# Tannenbaum.net
KiCad netlist of a schematic drawn in EAGLE
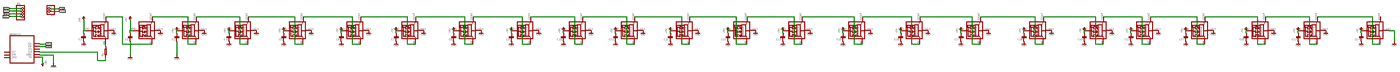
[diagram p0: schematic, sheet 1, overview]
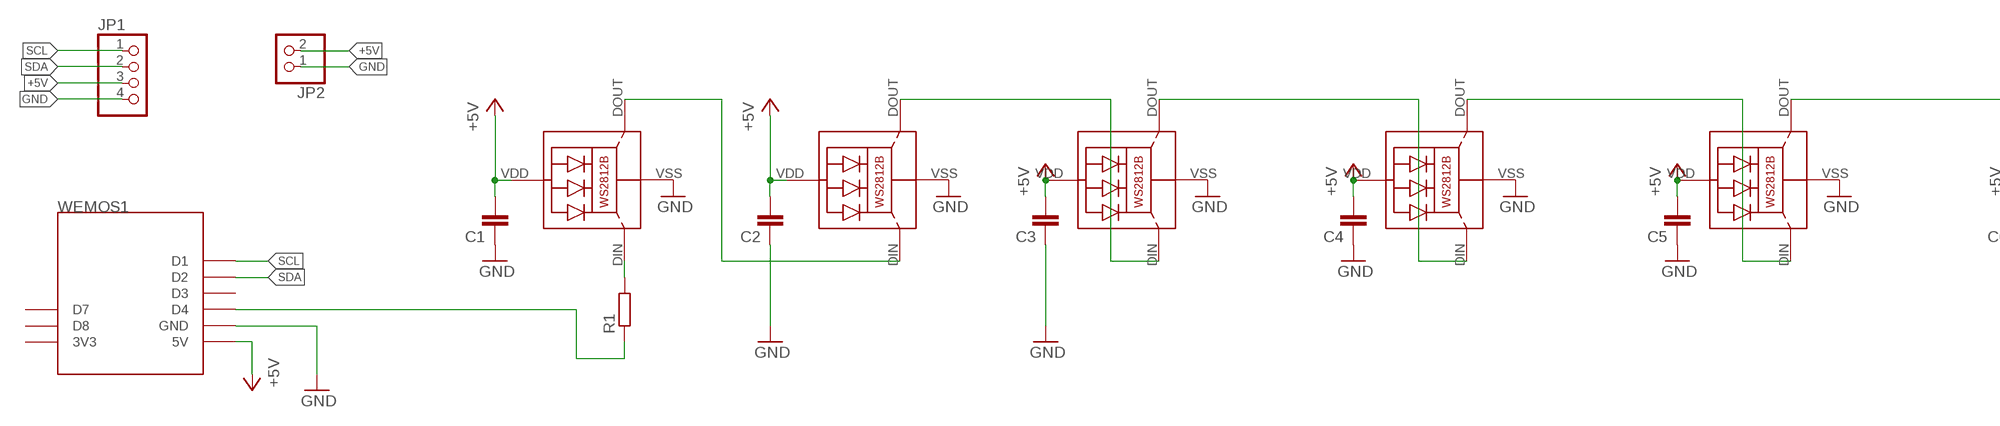
[diagram p1: schematic, sheet 1, part 1 of 4]
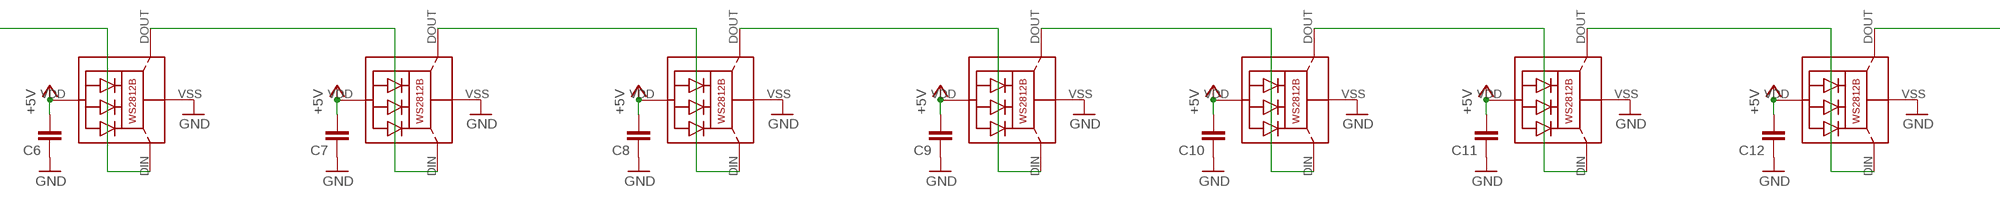
[diagram p2: schematic, sheet 1, part 2 of 4]
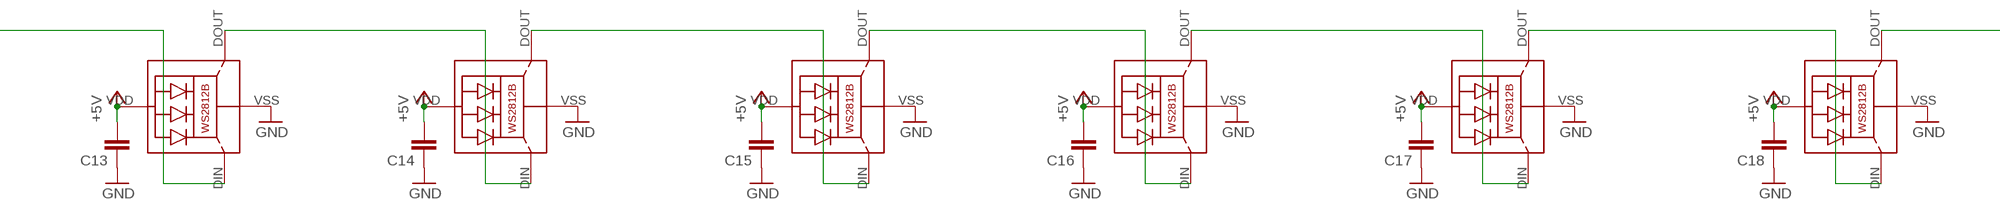
[diagram p3: schematic, sheet 1, part 3 of 4]
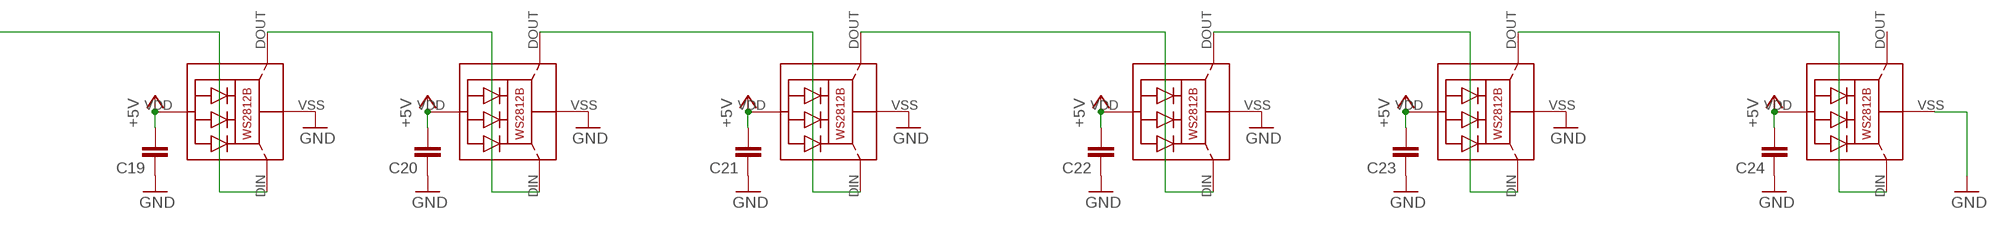
[diagram p4: schematic, sheet 1, part 4 of 4]

(export (version "E")
  (design (tool "Eeschema 10.0.6"))
  (components
    (comp (ref "C1")
      (value "C-EUC0805")
      (footprint "eagle-import:C0805")
      (libsource (lib "eagle-import") (part "C-EUC0805"))
    )
    (comp (ref "C2")
      (value "C-EUC0805")
      (footprint "eagle-import:C0805")
      (libsource (lib "eagle-import") (part "C-EUC0805"))
    )
    (comp (ref "C3")
      (value "C-EUC0805")
      (footprint "eagle-import:C0805")
      (libsource (lib "eagle-import") (part "C-EUC0805"))
    )
    (comp (ref "C4")
      (value "C-EUC0805")
      (footprint "eagle-import:C0805")
      (libsource (lib "eagle-import") (part "C-EUC0805"))
    )
    (comp (ref "C5")
      (value "C-EUC0805")
      (footprint "eagle-import:C0805")
      (libsource (lib "eagle-import") (part "C-EUC0805"))
    )
    (comp (ref "C6")
      (value "C-EUC0805")
      (footprint "eagle-import:C0805")
      (libsource (lib "eagle-import") (part "C-EUC0805"))
    )
    (comp (ref "C7")
      (value "C-EUC0805")
      (footprint "eagle-import:C0805")
      (libsource (lib "eagle-import") (part "C-EUC0805"))
    )
    (comp (ref "C8")
      (value "C-EUC0805")
      (footprint "eagle-import:C0805")
      (libsource (lib "eagle-import") (part "C-EUC0805"))
    )
    (comp (ref "C9")
      (value "C-EUC0805")
      (footprint "eagle-import:C0805")
      (libsource (lib "eagle-import") (part "C-EUC0805"))
    )
    (comp (ref "C10")
      (value "C-EUC0805")
      (footprint "eagle-import:C0805")
      (libsource (lib "eagle-import") (part "C-EUC0805"))
    )
    (comp (ref "C11")
      (value "C-EUC0805")
      (footprint "eagle-import:C0805")
      (libsource (lib "eagle-import") (part "C-EUC0805"))
    )
    (comp (ref "C12")
      (value "C-EUC0805")
      (footprint "eagle-import:C0805")
      (libsource (lib "eagle-import") (part "C-EUC0805"))
    )
    (comp (ref "C13")
      (value "C-EUC0805")
      (footprint "eagle-import:C0805")
      (libsource (lib "eagle-import") (part "C-EUC0805"))
    )
    (comp (ref "C14")
      (value "C-EUC0805")
      (footprint "eagle-import:C0805")
      (libsource (lib "eagle-import") (part "C-EUC0805"))
    )
    (comp (ref "C15")
      (value "C-EUC0805")
      (footprint "eagle-import:C0805")
      (libsource (lib "eagle-import") (part "C-EUC0805"))
    )
    (comp (ref "C16")
      (value "C-EUC0805")
      (footprint "eagle-import:C0805")
      (libsource (lib "eagle-import") (part "C-EUC0805"))
    )
    (comp (ref "C17")
      (value "C-EUC0805")
      (footprint "eagle-import:C0805")
      (libsource (lib "eagle-import") (part "C-EUC0805"))
    )
    (comp (ref "C18")
      (value "C-EUC0805")
      (footprint "eagle-import:C0805")
      (libsource (lib "eagle-import") (part "C-EUC0805"))
    )
    (comp (ref "C19")
      (value "C-EUC0805")
      (footprint "eagle-import:C0805")
      (libsource (lib "eagle-import") (part "C-EUC0805"))
    )
    (comp (ref "C20")
      (value "C-EUC0805")
      (footprint "eagle-import:C0805")
      (libsource (lib "eagle-import") (part "C-EUC0805"))
    )
    (comp (ref "C21")
      (value "C-EUC0805")
      (footprint "eagle-import:C0805")
      (libsource (lib "eagle-import") (part "C-EUC0805"))
    )
    (comp (ref "C22")
      (value "C-EUC0805")
      (footprint "eagle-import:C0805")
      (libsource (lib "eagle-import") (part "C-EUC0805"))
    )
    (comp (ref "C23")
      (value "C-EUC0805")
      (footprint "eagle-import:C0805")
      (libsource (lib "eagle-import") (part "C-EUC0805"))
    )
    (comp (ref "C24")
      (value "C-EUC0805")
      (footprint "eagle-import:C0805")
      (libsource (lib "eagle-import") (part "C-EUC0805"))
    )
    (comp (ref "JP1")
      (value "PINHD-1X4")
      (footprint "eagle-import:1X04")
      (libsource (lib "eagle-import") (part "PINHD-1X4"))
    )
    (comp (ref "JP2")
      (value "PINHD-1X2")
      (footprint "eagle-import:1X02")
      (libsource (lib "eagle-import") (part "PINHD-1X2"))
    )
    (comp (ref "LED1")
      (value "WS2812B")
      (footprint "eagle-import:WS2812B")
      (libsource (lib "eagle-import") (part "WS2812B"))
    )
    (comp (ref "LED2")
      (value "WS2812B")
      (footprint "eagle-import:WS2812B")
      (libsource (lib "eagle-import") (part "WS2812B"))
    )
    (comp (ref "LED3")
      (value "WS2812B")
      (footprint "eagle-import:WS2812B")
      (libsource (lib "eagle-import") (part "WS2812B"))
    )
    (comp (ref "LED4")
      (value "WS2812B")
      (footprint "eagle-import:WS2812B")
      (libsource (lib "eagle-import") (part "WS2812B"))
    )
    (comp (ref "LED5")
      (value "WS2812B")
      (footprint "eagle-import:WS2812B")
      (libsource (lib "eagle-import") (part "WS2812B"))
    )
    (comp (ref "LED6")
      (value "WS2812B")
      (footprint "eagle-import:WS2812B")
      (libsource (lib "eagle-import") (part "WS2812B"))
    )
    (comp (ref "LED7")
      (value "WS2812B")
      (footprint "eagle-import:WS2812B")
      (libsource (lib "eagle-import") (part "WS2812B"))
    )
    (comp (ref "LED8")
      (value "WS2812B")
      (footprint "eagle-import:WS2812B")
      (libsource (lib "eagle-import") (part "WS2812B"))
    )
    (comp (ref "LED9")
      (value "WS2812B")
      (footprint "eagle-import:WS2812B")
      (libsource (lib "eagle-import") (part "WS2812B"))
    )
    (comp (ref "LED10")
      (value "WS2812B")
      (footprint "eagle-import:WS2812B")
      (libsource (lib "eagle-import") (part "WS2812B"))
    )
    (comp (ref "LED11")
      (value "WS2812B")
      (footprint "eagle-import:WS2812B")
      (libsource (lib "eagle-import") (part "WS2812B"))
    )
    (comp (ref "LED12")
      (value "WS2812B")
      (footprint "eagle-import:WS2812B")
      (libsource (lib "eagle-import") (part "WS2812B"))
    )
    (comp (ref "LED13")
      (value "WS2812B")
      (footprint "eagle-import:WS2812B")
      (libsource (lib "eagle-import") (part "WS2812B"))
    )
    (comp (ref "LED14")
      (value "WS2812B")
      (footprint "eagle-import:WS2812B")
      (libsource (lib "eagle-import") (part "WS2812B"))
    )
    (comp (ref "LED15")
      (value "WS2812B")
      (footprint "eagle-import:WS2812B")
      (libsource (lib "eagle-import") (part "WS2812B"))
    )
    (comp (ref "LED16")
      (value "WS2812B")
      (footprint "eagle-import:WS2812B")
      (libsource (lib "eagle-import") (part "WS2812B"))
    )
    (comp (ref "LED17")
      (value "WS2812B")
      (footprint "eagle-import:WS2812B")
      (libsource (lib "eagle-import") (part "WS2812B"))
    )
    (comp (ref "LED18")
      (value "WS2812B")
      (footprint "eagle-import:WS2812B")
      (libsource (lib "eagle-import") (part "WS2812B"))
    )
    (comp (ref "LED19")
      (value "WS2812B")
      (footprint "eagle-import:WS2812B")
      (libsource (lib "eagle-import") (part "WS2812B"))
    )
    (comp (ref "LED20")
      (value "WS2812B")
      (footprint "eagle-import:WS2812B")
      (libsource (lib "eagle-import") (part "WS2812B"))
    )
    (comp (ref "LED21")
      (value "WS2812B")
      (footprint "eagle-import:WS2812B")
      (libsource (lib "eagle-import") (part "WS2812B"))
    )
    (comp (ref "LED22")
      (value "WS2812B")
      (footprint "eagle-import:WS2812B")
      (libsource (lib "eagle-import") (part "WS2812B"))
    )
    (comp (ref "LED23")
      (value "WS2812B")
      (footprint "eagle-import:WS2812B")
      (libsource (lib "eagle-import") (part "WS2812B"))
    )
    (comp (ref "LED24")
      (value "WS2812B")
      (footprint "eagle-import:WS2812B")
      (libsource (lib "eagle-import") (part "WS2812B"))
    )
    (comp (ref "R1")
      (value "R-EU_R0805")
      (footprint "eagle-import:R0805")
      (libsource (lib "eagle-import") (part "R-EU_R0805"))
    )
    (comp (ref "WEMOS1")
      (value "WEMOS-D1-MINI1")
      (footprint "eagle-import:WEMOS-D1-MINI1")
      (fields (field (name "SPICEPREFIX") "X"))
      (libsource (lib "eagle-import") (part "WEMOS-D1-MINI1"))
    )
  )
  (nets
    (net (code "1") (name "+5V") (class "Default")
      (node (ref "C1") (pin "2") (pinfunction "2_2") (pintype "passive"))
      (node (ref "C10") (pin "2") (pinfunction "2_2") (pintype "passive"))
      (node (ref "C11") (pin "2") (pinfunction "2_2") (pintype "passive"))
      (node (ref "C12") (pin "2") (pinfunction "2_2") (pintype "passive"))
      (node (ref "C13") (pin "2") (pinfunction "2_2") (pintype "passive"))
      (node (ref "C14") (pin "2") (pinfunction "2_2") (pintype "passive"))
      (node (ref "C15") (pin "2") (pinfunction "2_2") (pintype "passive"))
      (node (ref "C16") (pin "2") (pinfunction "2_2") (pintype "passive"))
      (node (ref "C17") (pin "2") (pinfunction "2_2") (pintype "passive"))
      (node (ref "C18") (pin "2") (pinfunction "2_2") (pintype "passive"))
      (node (ref "C19") (pin "2") (pinfunction "2_2") (pintype "passive"))
      (node (ref "C2") (pin "2") (pinfunction "2_2") (pintype "passive"))
      (node (ref "C20") (pin "2") (pinfunction "2_2") (pintype "passive"))
      (node (ref "C21") (pin "2") (pinfunction "2_2") (pintype "passive"))
      (node (ref "C22") (pin "2") (pinfunction "2_2") (pintype "passive"))
      (node (ref "C23") (pin "2") (pinfunction "2_2") (pintype "passive"))
      (node (ref "C24") (pin "2") (pinfunction "2_2") (pintype "passive"))
      (node (ref "C3") (pin "2") (pinfunction "2_2") (pintype "passive"))
      (node (ref "C4") (pin "2") (pinfunction "2_2") (pintype "passive"))
      (node (ref "C5") (pin "2") (pinfunction "2_2") (pintype "passive"))
      (node (ref "C6") (pin "2") (pinfunction "2_2") (pintype "passive"))
      (node (ref "C7") (pin "2") (pinfunction "2_2") (pintype "passive"))
      (node (ref "C8") (pin "2") (pinfunction "2_2") (pintype "passive"))
      (node (ref "C9") (pin "2") (pinfunction "2_2") (pintype "passive"))
      (node (ref "JP1") (pin "3") (pinfunction "3_3") (pintype "passive"))
      (node (ref "JP2") (pin "2") (pinfunction "2_2") (pintype "passive"))
      (node (ref "LED1") (pin "VDD") (pinfunction "VDD_VDD") (pintype "power_in"))
      (node (ref "LED10") (pin "VDD") (pinfunction "VDD_VDD") (pintype "power_in"))
      (node (ref "LED11") (pin "VDD") (pinfunction "VDD_VDD") (pintype "power_in"))
      (node (ref "LED12") (pin "VDD") (pinfunction "VDD_VDD") (pintype "power_in"))
      (node (ref "LED13") (pin "VDD") (pinfunction "VDD_VDD") (pintype "power_in"))
      (node (ref "LED14") (pin "VDD") (pinfunction "VDD_VDD") (pintype "power_in"))
      (node (ref "LED15") (pin "VDD") (pinfunction "VDD_VDD") (pintype "power_in"))
      (node (ref "LED16") (pin "VDD") (pinfunction "VDD_VDD") (pintype "power_in"))
      (node (ref "LED17") (pin "VDD") (pinfunction "VDD_VDD") (pintype "power_in"))
      (node (ref "LED18") (pin "VDD") (pinfunction "VDD_VDD") (pintype "power_in"))
      (node (ref "LED19") (pin "VDD") (pinfunction "VDD_VDD") (pintype "power_in"))
      (node (ref "LED2") (pin "VDD") (pinfunction "VDD_VDD") (pintype "power_in"))
      (node (ref "LED20") (pin "VDD") (pinfunction "VDD_VDD") (pintype "power_in"))
      (node (ref "LED21") (pin "VDD") (pinfunction "VDD_VDD") (pintype "power_in"))
      (node (ref "LED22") (pin "VDD") (pinfunction "VDD_VDD") (pintype "power_in"))
      (node (ref "LED23") (pin "VDD") (pinfunction "VDD_VDD") (pintype "power_in"))
      (node (ref "LED24") (pin "VDD") (pinfunction "VDD_VDD") (pintype "power_in"))
      (node (ref "LED3") (pin "VDD") (pinfunction "VDD_VDD") (pintype "power_in"))
      (node (ref "LED4") (pin "VDD") (pinfunction "VDD_VDD") (pintype "power_in"))
      (node (ref "LED5") (pin "VDD") (pinfunction "VDD_VDD") (pintype "power_in"))
      (node (ref "LED6") (pin "VDD") (pinfunction "VDD_VDD") (pintype "power_in"))
      (node (ref "LED7") (pin "VDD") (pinfunction "VDD_VDD") (pintype "power_in"))
      (node (ref "LED8") (pin "VDD") (pinfunction "VDD_VDD") (pintype "power_in"))
      (node (ref "LED9") (pin "VDD") (pinfunction "VDD_VDD") (pintype "power_in"))
      (node (ref "WEMOS1") (pin "5V") (pinfunction "5V_5V") (pintype "bidirectional"))
    )
    (net (code "2") (name "GND") (class "Default")
      (node (ref "C1") (pin "1") (pinfunction "1_1") (pintype "passive"))
      (node (ref "C10") (pin "1") (pinfunction "1_1") (pintype "passive"))
      (node (ref "C11") (pin "1") (pinfunction "1_1") (pintype "passive"))
      (node (ref "C12") (pin "1") (pinfunction "1_1") (pintype "passive"))
      (node (ref "C13") (pin "1") (pinfunction "1_1") (pintype "passive"))
      (node (ref "C14") (pin "1") (pinfunction "1_1") (pintype "passive"))
      (node (ref "C15") (pin "1") (pinfunction "1_1") (pintype "passive"))
      (node (ref "C16") (pin "1") (pinfunction "1_1") (pintype "passive"))
      (node (ref "C17") (pin "1") (pinfunction "1_1") (pintype "passive"))
      (node (ref "C18") (pin "1") (pinfunction "1_1") (pintype "passive"))
      (node (ref "C19") (pin "1") (pinfunction "1_1") (pintype "passive"))
      (node (ref "C2") (pin "1") (pinfunction "1_1") (pintype "passive"))
      (node (ref "C20") (pin "1") (pinfunction "1_1") (pintype "passive"))
      (node (ref "C21") (pin "1") (pinfunction "1_1") (pintype "passive"))
      (node (ref "C22") (pin "1") (pinfunction "1_1") (pintype "passive"))
      (node (ref "C23") (pin "1") (pinfunction "1_1") (pintype "passive"))
      (node (ref "C24") (pin "1") (pinfunction "1_1") (pintype "passive"))
      (node (ref "C3") (pin "1") (pinfunction "1_1") (pintype "passive"))
      (node (ref "C4") (pin "1") (pinfunction "1_1") (pintype "passive"))
      (node (ref "C5") (pin "1") (pinfunction "1_1") (pintype "passive"))
      (node (ref "C6") (pin "1") (pinfunction "1_1") (pintype "passive"))
      (node (ref "C7") (pin "1") (pinfunction "1_1") (pintype "passive"))
      (node (ref "C8") (pin "1") (pinfunction "1_1") (pintype "passive"))
      (node (ref "C9") (pin "1") (pinfunction "1_1") (pintype "passive"))
      (node (ref "JP1") (pin "4") (pinfunction "4_4") (pintype "passive"))
      (node (ref "JP2") (pin "1") (pinfunction "1_1") (pintype "passive"))
      (node (ref "LED1") (pin "VSS") (pinfunction "GND_VSS") (pintype "power_in"))
      (node (ref "LED10") (pin "VSS") (pinfunction "GND_VSS") (pintype "power_in"))
      (node (ref "LED11") (pin "VSS") (pinfunction "GND_VSS") (pintype "power_in"))
      (node (ref "LED12") (pin "VSS") (pinfunction "GND_VSS") (pintype "power_in"))
      (node (ref "LED13") (pin "VSS") (pinfunction "GND_VSS") (pintype "power_in"))
      (node (ref "LED14") (pin "VSS") (pinfunction "GND_VSS") (pintype "power_in"))
      (node (ref "LED15") (pin "VSS") (pinfunction "GND_VSS") (pintype "power_in"))
      (node (ref "LED16") (pin "VSS") (pinfunction "GND_VSS") (pintype "power_in"))
      (node (ref "LED17") (pin "VSS") (pinfunction "GND_VSS") (pintype "power_in"))
      (node (ref "LED18") (pin "VSS") (pinfunction "GND_VSS") (pintype "power_in"))
      (node (ref "LED19") (pin "VSS") (pinfunction "GND_VSS") (pintype "power_in"))
      (node (ref "LED2") (pin "VSS") (pinfunction "GND_VSS") (pintype "power_in"))
      (node (ref "LED20") (pin "VSS") (pinfunction "GND_VSS") (pintype "power_in"))
      (node (ref "LED21") (pin "VSS") (pinfunction "GND_VSS") (pintype "power_in"))
      (node (ref "LED22") (pin "VSS") (pinfunction "GND_VSS") (pintype "power_in"))
      (node (ref "LED23") (pin "VSS") (pinfunction "GND_VSS") (pintype "power_in"))
      (node (ref "LED24") (pin "VSS") (pinfunction "GND_VSS") (pintype "power_in"))
      (node (ref "LED3") (pin "VSS") (pinfunction "GND_VSS") (pintype "power_in"))
      (node (ref "LED4") (pin "VSS") (pinfunction "GND_VSS") (pintype "power_in"))
      (node (ref "LED5") (pin "VSS") (pinfunction "GND_VSS") (pintype "power_in"))
      (node (ref "LED6") (pin "VSS") (pinfunction "GND_VSS") (pintype "power_in"))
      (node (ref "LED7") (pin "VSS") (pinfunction "GND_VSS") (pintype "power_in"))
      (node (ref "LED8") (pin "VSS") (pinfunction "GND_VSS") (pintype "power_in"))
      (node (ref "LED9") (pin "VSS") (pinfunction "GND_VSS") (pintype "power_in"))
      (node (ref "WEMOS1") (pin "GND") (pinfunction "GND_GND") (pintype "bidirectional"))
    )
    (net (code "3") (name "Net-(LED1-DI)") (class "Default")
      (node (ref "LED1") (pin "DIN") (pinfunction "DI_DIN") (pintype "input"))
      (node (ref "R1") (pin "2") (pinfunction "2_2") (pintype "passive"))
    )
    (net (code "4") (name "Net-(LED1-DO)") (class "Default")
      (node (ref "LED1") (pin "DOUT") (pinfunction "DO_DOUT") (pintype "output"))
      (node (ref "LED2") (pin "DIN") (pinfunction "DI_DIN") (pintype "input"))
    )
    (net (code "5") (name "Net-(LED2-DO)") (class "Default")
      (node (ref "LED2") (pin "DOUT") (pinfunction "DO_DOUT") (pintype "output"))
      (node (ref "LED3") (pin "DIN") (pinfunction "DI_DIN") (pintype "input"))
    )
    (net (code "6") (name "Net-(LED3-DO)") (class "Default")
      (node (ref "LED3") (pin "DOUT") (pinfunction "DO_DOUT") (pintype "output"))
      (node (ref "LED4") (pin "DIN") (pinfunction "DI_DIN") (pintype "input"))
    )
    (net (code "7") (name "Net-(LED4-DO)") (class "Default")
      (node (ref "LED4") (pin "DOUT") (pinfunction "DO_DOUT") (pintype "output"))
      (node (ref "LED5") (pin "DIN") (pinfunction "DI_DIN") (pintype "input"))
    )
    (net (code "8") (name "Net-(LED5-DO)") (class "Default")
      (node (ref "LED5") (pin "DOUT") (pinfunction "DO_DOUT") (pintype "output"))
      (node (ref "LED6") (pin "DIN") (pinfunction "DI_DIN") (pintype "input"))
    )
    (net (code "9") (name "Net-(LED6-DO)") (class "Default")
      (node (ref "LED6") (pin "DOUT") (pinfunction "DO_DOUT") (pintype "output"))
      (node (ref "LED7") (pin "DIN") (pinfunction "DI_DIN") (pintype "input"))
    )
    (net (code "10") (name "Net-(LED7-DO)") (class "Default")
      (node (ref "LED7") (pin "DOUT") (pinfunction "DO_DOUT") (pintype "output"))
      (node (ref "LED8") (pin "DIN") (pinfunction "DI_DIN") (pintype "input"))
    )
    (net (code "11") (name "Net-(LED8-DO)") (class "Default")
      (node (ref "LED8") (pin "DOUT") (pinfunction "DO_DOUT") (pintype "output"))
      (node (ref "LED9") (pin "DIN") (pinfunction "DI_DIN") (pintype "input"))
    )
    (net (code "12") (name "Net-(LED10-DI)") (class "Default")
      (node (ref "LED10") (pin "DIN") (pinfunction "DI_DIN") (pintype "input"))
      (node (ref "LED9") (pin "DOUT") (pinfunction "DO_DOUT") (pintype "output"))
    )
    (net (code "13") (name "Net-(LED10-DO)") (class "Default")
      (node (ref "LED10") (pin "DOUT") (pinfunction "DO_DOUT") (pintype "output"))
      (node (ref "LED11") (pin "DIN") (pinfunction "DI_DIN") (pintype "input"))
    )
    (net (code "14") (name "Net-(LED11-DO)") (class "Default")
      (node (ref "LED11") (pin "DOUT") (pinfunction "DO_DOUT") (pintype "output"))
      (node (ref "LED12") (pin "DIN") (pinfunction "DI_DIN") (pintype "input"))
    )
    (net (code "15") (name "Net-(LED12-DO)") (class "Default")
      (node (ref "LED12") (pin "DOUT") (pinfunction "DO_DOUT") (pintype "output"))
      (node (ref "LED13") (pin "DIN") (pinfunction "DI_DIN") (pintype "input"))
    )
    (net (code "16") (name "Net-(LED13-DO)") (class "Default")
      (node (ref "LED13") (pin "DOUT") (pinfunction "DO_DOUT") (pintype "output"))
      (node (ref "LED14") (pin "DIN") (pinfunction "DI_DIN") (pintype "input"))
    )
    (net (code "17") (name "Net-(LED14-DO)") (class "Default")
      (node (ref "LED14") (pin "DOUT") (pinfunction "DO_DOUT") (pintype "output"))
      (node (ref "LED15") (pin "DIN") (pinfunction "DI_DIN") (pintype "input"))
    )
    (net (code "18") (name "Net-(LED15-DO)") (class "Default")
      (node (ref "LED15") (pin "DOUT") (pinfunction "DO_DOUT") (pintype "output"))
      (node (ref "LED16") (pin "DIN") (pinfunction "DI_DIN") (pintype "input"))
    )
    (net (code "19") (name "Net-(LED16-DO)") (class "Default")
      (node (ref "LED16") (pin "DOUT") (pinfunction "DO_DOUT") (pintype "output"))
      (node (ref "LED17") (pin "DIN") (pinfunction "DI_DIN") (pintype "input"))
    )
    (net (code "20") (name "Net-(LED17-DO)") (class "Default")
      (node (ref "LED17") (pin "DOUT") (pinfunction "DO_DOUT") (pintype "output"))
      (node (ref "LED18") (pin "DIN") (pinfunction "DI_DIN") (pintype "input"))
    )
    (net (code "21") (name "Net-(LED18-DO)") (class "Default")
      (node (ref "LED18") (pin "DOUT") (pinfunction "DO_DOUT") (pintype "output"))
      (node (ref "LED19") (pin "DIN") (pinfunction "DI_DIN") (pintype "input"))
    )
    (net (code "22") (name "Net-(LED19-DO)") (class "Default")
      (node (ref "LED19") (pin "DOUT") (pinfunction "DO_DOUT") (pintype "output"))
      (node (ref "LED20") (pin "DIN") (pinfunction "DI_DIN") (pintype "input"))
    )
    (net (code "23") (name "Net-(LED20-DO)") (class "Default")
      (node (ref "LED20") (pin "DOUT") (pinfunction "DO_DOUT") (pintype "output"))
      (node (ref "LED21") (pin "DIN") (pinfunction "DI_DIN") (pintype "input"))
    )
    (net (code "24") (name "Net-(LED21-DO)") (class "Default")
      (node (ref "LED21") (pin "DOUT") (pinfunction "DO_DOUT") (pintype "output"))
      (node (ref "LED22") (pin "DIN") (pinfunction "DI_DIN") (pintype "input"))
    )
    (net (code "25") (name "Net-(LED22-DO)") (class "Default")
      (node (ref "LED22") (pin "DOUT") (pinfunction "DO_DOUT") (pintype "output"))
      (node (ref "LED23") (pin "DIN") (pinfunction "DI_DIN") (pintype "input"))
    )
    (net (code "26") (name "Net-(LED23-DO)") (class "Default")
      (node (ref "LED23") (pin "DOUT") (pinfunction "DO_DOUT") (pintype "output"))
      (node (ref "LED24") (pin "DIN") (pinfunction "DI_DIN") (pintype "input"))
    )
    (net (code "27") (name "Net-(R1-Pad1)") (class "Default")
      (node (ref "R1") (pin "1") (pinfunction "1_1") (pintype "passive"))
      (node (ref "WEMOS1") (pin "D4") (pinfunction "D4_D4") (pintype "bidirectional"))
    )
    (net (code "28") (name "SCL") (class "Default")
      (node (ref "JP1") (pin "1") (pinfunction "1_1") (pintype "passive"))
      (node (ref "WEMOS1") (pin "D1") (pinfunction "D1_D1") (pintype "bidirectional"))
    )
    (net (code "29") (name "SDA") (class "Default")
      (node (ref "JP1") (pin "2") (pinfunction "2_2") (pintype "passive"))
      (node (ref "WEMOS1") (pin "D2") (pinfunction "D2_D2") (pintype "bidirectional"))
    )
    (net (code "30") (name "unconnected-(LED24-DO-PadDOUT)") (class "Default")
      (node (ref "LED24") (pin "DOUT") (pinfunction "DO_DOUT") (pintype "output"))
    )
    (net (code "31") (name "unconnected-(WEMOS1-Pad3V3)") (class "Default")
      (node (ref "WEMOS1") (pin "3V3") (pinfunction "3V3_3V3") (pintype "bidirectional"))
    )
    (net (code "32") (name "unconnected-(WEMOS1-PadD3)") (class "Default")
      (node (ref "WEMOS1") (pin "D3") (pinfunction "D3_D3") (pintype "bidirectional"))
    )
    (net (code "33") (name "unconnected-(WEMOS1-PadD7)") (class "Default")
      (node (ref "WEMOS1") (pin "D7") (pinfunction "D7_D7") (pintype "bidirectional"))
    )
    (net (code "34") (name "unconnected-(WEMOS1-PadD8)") (class "Default")
      (node (ref "WEMOS1") (pin "D8") (pinfunction "D8_D8") (pintype "bidirectional"))
    )
  )
)
